# humidor_controller_v31.net
KiCad netlist of a schematic drawn in EAGLE
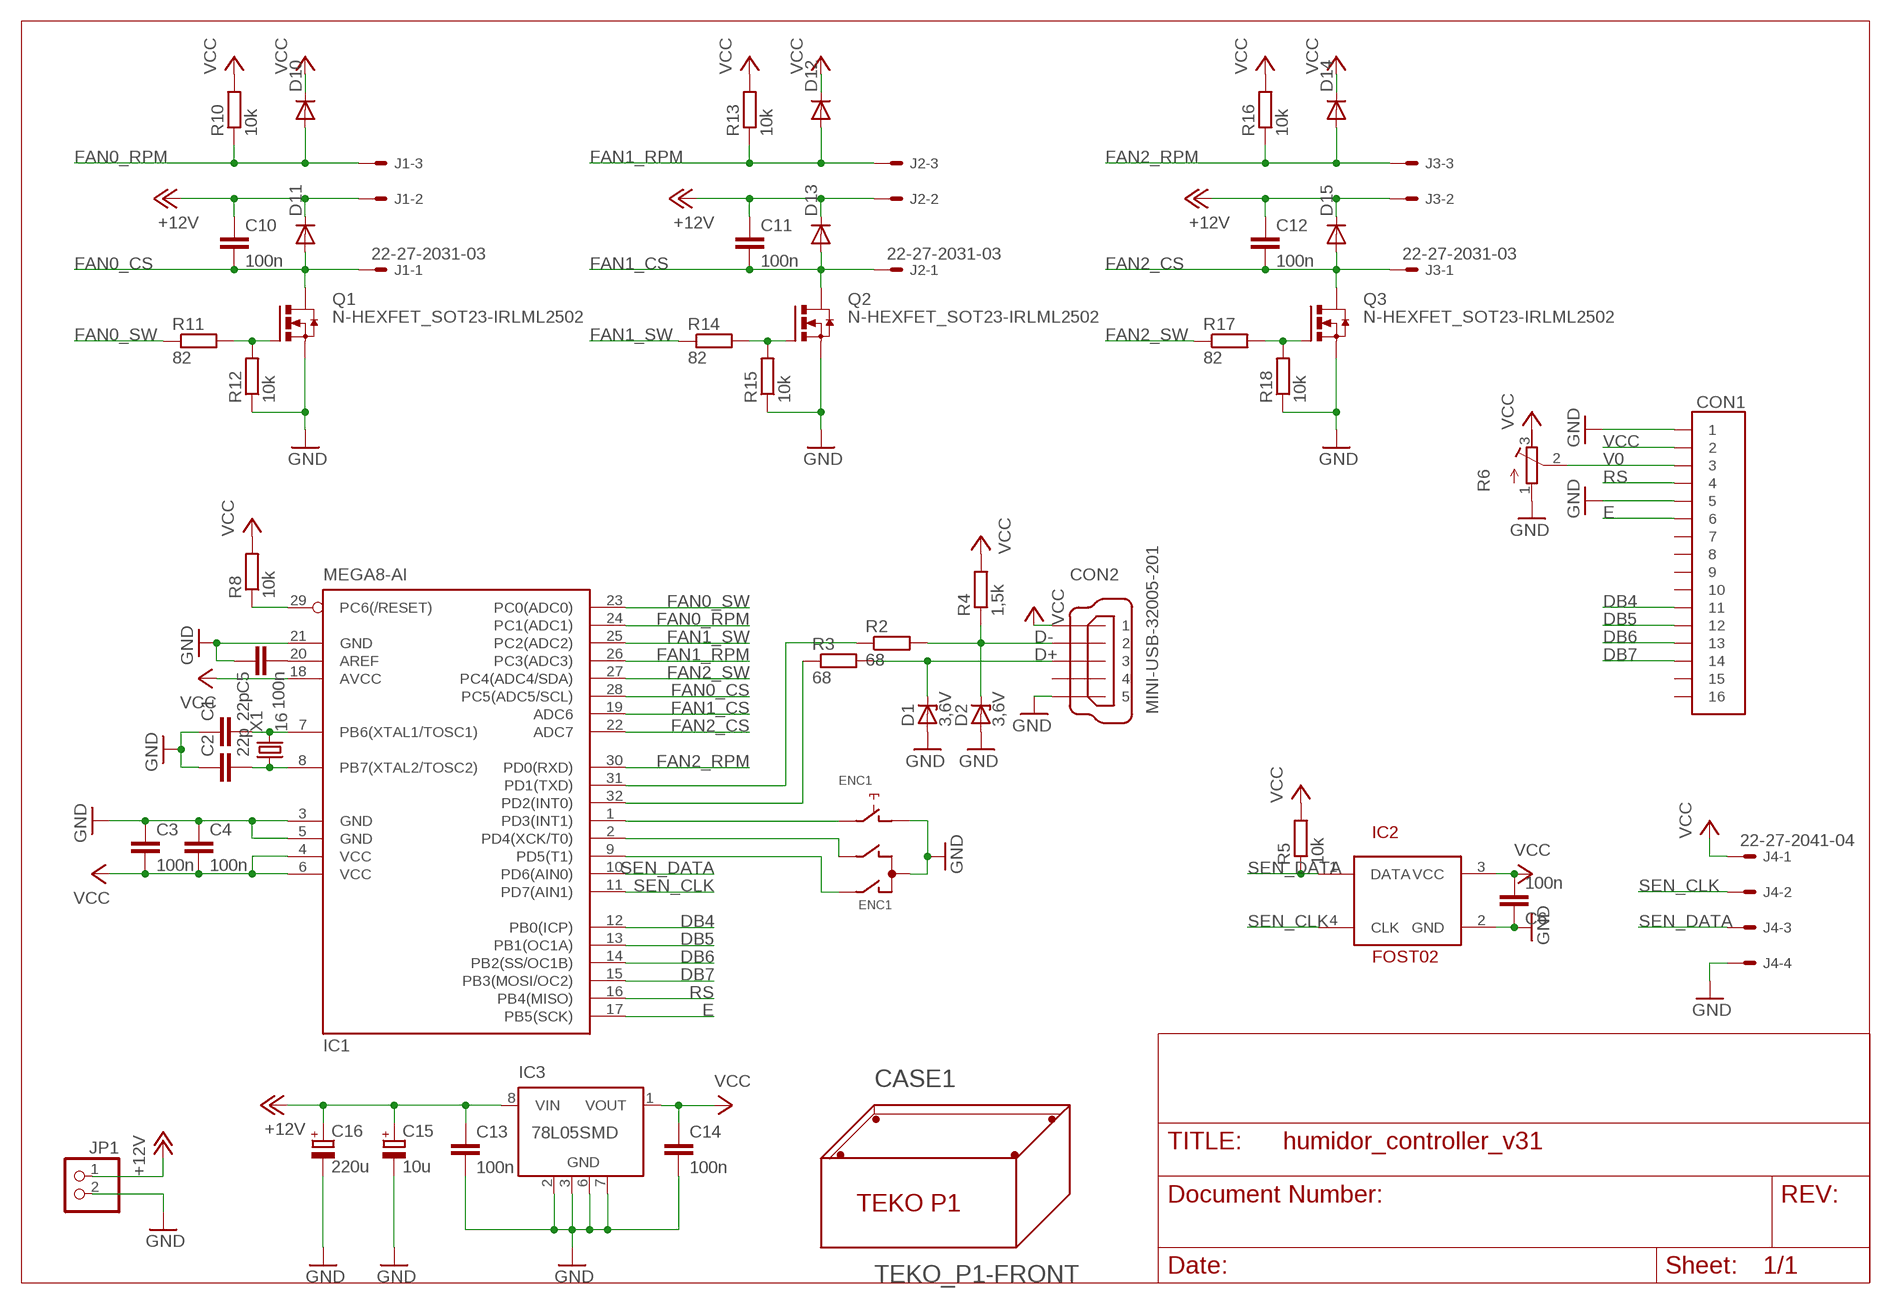
[diagram p0: schematic, sheet 1]

(export (version "E")
  (design (tool "Eeschema 10.0.6"))
  (components
    (comp (ref "C1")
      (value "22p")
      (footprint "eagle-import:C0805")
      (libsource (lib "eagle-import") (part "C-EUC0805"))
    )
    (comp (ref "C2")
      (value "22p")
      (footprint "eagle-import:C0805")
      (libsource (lib "eagle-import") (part "C-EUC0805"))
    )
    (comp (ref "C3")
      (value "100n")
      (footprint "eagle-import:C0805")
      (libsource (lib "eagle-import") (part "resistor_C-EUC0805"))
    )
    (comp (ref "C4")
      (value "100n")
      (footprint "eagle-import:C0805")
      (libsource (lib "eagle-import") (part "resistor_C-EUC0805"))
    )
    (comp (ref "C5")
      (value "100n")
      (footprint "eagle-import:C0805")
      (libsource (lib "eagle-import") (part "resistor_C-EUC0805"))
    )
    (comp (ref "C6")
      (value "100n")
      (footprint "eagle-import:C0805")
      (libsource (lib "eagle-import") (part "resistor_C-EUC0805"))
    )
    (comp (ref "C10")
      (value "100n")
      (footprint "eagle-import:C0805")
      (libsource (lib "eagle-import") (part "resistor_C-EUC0805"))
    )
    (comp (ref "C11")
      (value "100n")
      (footprint "eagle-import:C0805")
      (libsource (lib "eagle-import") (part "resistor_C-EUC0805"))
    )
    (comp (ref "C12")
      (value "100n")
      (footprint "eagle-import:C0805")
      (libsource (lib "eagle-import") (part "resistor_C-EUC0805"))
    )
    (comp (ref "C13")
      (value "100n")
      (footprint "eagle-import:C0805")
      (libsource (lib "eagle-import") (part "C-EUC0805"))
    )
    (comp (ref "C14")
      (value "100n")
      (footprint "eagle-import:C0805")
      (libsource (lib "eagle-import") (part "C-EUC0805"))
    )
    (comp (ref "C15")
      (value "10u")
      (footprint "eagle-import:PANASONIC_D")
      (libsource (lib "eagle-import") (part "CPOL-EUD"))
    )
    (comp (ref "C16")
      (value "220u")
      (footprint "eagle-import:PANASONIC_G")
      (libsource (lib "eagle-import") (part "CPOL-EUG"))
    )
    (comp (ref "CASE1")
      (value "TEKO_P1-FRONT")
      (footprint "eagle-import:TEKO_P1_FRONT")
      (libsource (lib "eagle-import") (part "TEKO_P1-FRONT"))
    )
    (comp (ref "CON1")
      (value "52207-16")
      (footprint "eagle-import:52207-16")
      (libsource (lib "eagle-import") (part "52207-16"))
    )
    (comp (ref "CON2")
      (value "MINI-USB-32005-201")
      (footprint "eagle-import:32005-201")
      (libsource (lib "eagle-import") (part "MINI-USB-32005-201"))
    )
    (comp (ref "D1")
      (value "3,6V")
      (footprint "eagle-import:SOD80C")
      (libsource (lib "eagle-import") (part "ZENER-DIODESOD80C"))
    )
    (comp (ref "D2")
      (value "3,6V")
      (footprint "eagle-import:SOD80C")
      (libsource (lib "eagle-import") (part "ZENER-DIODESOD80C"))
    )
    (comp (ref "D10")
      (value "DIODE-SOD323-R")
      (footprint "eagle-import:SOD323-R")
      (libsource (lib "eagle-import") (part "DIODE-SOD323-R"))
    )
    (comp (ref "D11")
      (value "DIODE-SOD323-R")
      (footprint "eagle-import:SOD323-R")
      (libsource (lib "eagle-import") (part "DIODE-SOD323-R"))
    )
    (comp (ref "D12")
      (value "DIODE-SOD323-R")
      (footprint "eagle-import:SOD323-R")
      (libsource (lib "eagle-import") (part "DIODE-SOD323-R"))
    )
    (comp (ref "D13")
      (value "DIODE-SOD323-R")
      (footprint "eagle-import:SOD323-R")
      (libsource (lib "eagle-import") (part "DIODE-SOD323-R"))
    )
    (comp (ref "D14")
      (value "DIODE-SOD323-R")
      (footprint "eagle-import:SOD323-R")
      (libsource (lib "eagle-import") (part "DIODE-SOD323-R"))
    )
    (comp (ref "D15")
      (value "DIODE-SOD323-R")
      (footprint "eagle-import:SOD323-R")
      (libsource (lib "eagle-import") (part "DIODE-SOD323-R"))
    )
    (comp (ref "ENC1")
      (value "NOBLE_RE0124")
      (footprint "eagle-import:RE0124")
      (libsource (lib "eagle-import") (part "NOBLE_RE0124"))
    )
    (comp (ref "IC1")
      (value "MEGA8-AI")
      (footprint "eagle-import:TQFP32-08")
      (libsource (lib "eagle-import") (part "MEGA8-AI"))
    )
    (comp (ref "IC2")
      (value "FOST02")
      (footprint "eagle-import:FOST02")
      (libsource (lib "eagle-import") (part "FOST02"))
    )
    (comp (ref "IC3")
      (value "78L05SMD")
      (footprint "eagle-import:SO08")
      (libsource (lib "eagle-import") (part "78LSMD05"))
    )
    (comp (ref "J1")
      (value "22-27-2031-03")
      (footprint "eagle-import:6410-03")
      (libsource (lib "eagle-import") (part "22-?-0327-2031"))
    )
    (comp (ref "J2")
      (value "22-27-2031-03")
      (footprint "eagle-import:6410-03")
      (libsource (lib "eagle-import") (part "22-?-0327-2031"))
    )
    (comp (ref "J3")
      (value "22-27-2031-03")
      (footprint "eagle-import:6410-03")
      (libsource (lib "eagle-import") (part "22-?-0327-2031"))
    )
    (comp (ref "J4")
      (value "22-27-2041-04")
      (footprint "eagle-import:6410-04")
      (libsource (lib "eagle-import") (part "22-?-0427-2041"))
    )
    (comp (ref "JP1")
      (value "PINHD-1X2")
      (footprint "eagle-import:1X02")
      (libsource (lib "eagle-import") (part "PINHD-1X2"))
    )
    (comp (ref "Q1")
      (value "N-HEXFET_SOT23-IRLML2502")
      (footprint "eagle-import:SOT23")
      (libsource (lib "eagle-import") (part "N-HEXFET_?-SOT23IRLML2502"))
    )
    (comp (ref "Q2")
      (value "N-HEXFET_SOT23-IRLML2502")
      (footprint "eagle-import:SOT23")
      (libsource (lib "eagle-import") (part "N-HEXFET_?-SOT23IRLML2502"))
    )
    (comp (ref "Q3")
      (value "N-HEXFET_SOT23-IRLML2502")
      (footprint "eagle-import:SOT23")
      (libsource (lib "eagle-import") (part "N-HEXFET_?-SOT23IRLML2502"))
    )
    (comp (ref "R2")
      (value "68")
      (footprint "eagle-import:R0805")
      (libsource (lib "eagle-import") (part "R-EU_R0805"))
    )
    (comp (ref "R3")
      (value "68")
      (footprint "eagle-import:R0805")
      (libsource (lib "eagle-import") (part "R-EU_R0805"))
    )
    (comp (ref "R4")
      (value "1,5k")
      (footprint "eagle-import:R0805")
      (libsource (lib "eagle-import") (part "R-EU_R0805"))
    )
    (comp (ref "R5")
      (value "10k")
      (footprint "eagle-import:R0805")
      (libsource (lib "eagle-import") (part "R-EU_R0805"))
    )
    (comp (ref "R6")
      (value "R-TRIMM4G/J")
      (footprint "eagle-import:RTRIM4G_J")
      (libsource (lib "eagle-import") (part "R-TRIMM4G/J"))
    )
    (comp (ref "R8")
      (value "10k")
      (footprint "eagle-import:R0805")
      (libsource (lib "eagle-import") (part "R-EU_R0805"))
    )
    (comp (ref "R10")
      (value "10k")
      (footprint "eagle-import:R0805")
      (libsource (lib "eagle-import") (part "R-EU_R0805"))
    )
    (comp (ref "R11")
      (value "82")
      (footprint "eagle-import:R0805")
      (libsource (lib "eagle-import") (part "R-EU_R0805"))
    )
    (comp (ref "R12")
      (value "10k")
      (footprint "eagle-import:R0805")
      (libsource (lib "eagle-import") (part "R-EU_R0805"))
    )
    (comp (ref "R13")
      (value "10k")
      (footprint "eagle-import:R0805")
      (libsource (lib "eagle-import") (part "R-EU_R0805"))
    )
    (comp (ref "R14")
      (value "82")
      (footprint "eagle-import:R0805")
      (libsource (lib "eagle-import") (part "R-EU_R0805"))
    )
    (comp (ref "R15")
      (value "10k")
      (footprint "eagle-import:R0805")
      (libsource (lib "eagle-import") (part "R-EU_R0805"))
    )
    (comp (ref "R16")
      (value "10k")
      (footprint "eagle-import:R0805")
      (libsource (lib "eagle-import") (part "R-EU_R0805"))
    )
    (comp (ref "R17")
      (value "82")
      (footprint "eagle-import:R0805")
      (libsource (lib "eagle-import") (part "R-EU_R0805"))
    )
    (comp (ref "R18")
      (value "10k")
      (footprint "eagle-import:R0805")
      (libsource (lib "eagle-import") (part "R-EU_R0805"))
    )
    (comp (ref "X1")
      (value "16")
      (footprint "eagle-import:HC49UP")
      (libsource (lib "eagle-import") (part "CRYSTALHC49UP"))
    )
  )
  (nets
    (net (code "1") (name "+12V") (class "Default")
      (node (ref "C10") (pin "1") (pinfunction "1_1") (pintype "passive"))
      (node (ref "C11") (pin "1") (pinfunction "1_1") (pintype "passive"))
      (node (ref "C12") (pin "1") (pinfunction "1_1") (pintype "passive"))
      (node (ref "C13") (pin "1") (pinfunction "1_1") (pintype "passive"))
      (node (ref "C15") (pin "+") (pinfunction "+_+") (pintype "passive"))
      (node (ref "C16") (pin "+") (pinfunction "+_+") (pintype "passive"))
      (node (ref "D11") (pin "C") (pinfunction "C_C") (pintype "passive"))
      (node (ref "D13") (pin "C") (pinfunction "C_C") (pintype "passive"))
      (node (ref "D15") (pin "C") (pinfunction "C_C") (pintype "passive"))
      (node (ref "IC3") (pin "8") (pinfunction "VIN_8") (pintype "passive"))
      (node (ref "J1") (pin "2") (pinfunction "S_2") (pintype "passive"))
      (node (ref "J2") (pin "2") (pinfunction "S_2") (pintype "passive"))
      (node (ref "J3") (pin "2") (pinfunction "S_2") (pintype "passive"))
      (node (ref "JP1") (pin "1") (pinfunction "1_1") (pintype "passive"))
    )
    (net (code "2") (name "/D+") (class "Default")
      (node (ref "CON2") (pin "3") (pinfunction "3_3") (pintype "passive"))
      (node (ref "D1") (pin "C") (pinfunction "C_C") (pintype "passive"))
      (node (ref "R3") (pin "2") (pinfunction "2_2") (pintype "passive"))
    )
    (net (code "3") (name "/D-") (class "Default")
      (node (ref "CON2") (pin "2") (pinfunction "2_2") (pintype "passive"))
      (node (ref "D2") (pin "C") (pinfunction "C_C") (pintype "passive"))
      (node (ref "R2") (pin "2") (pinfunction "2_2") (pintype "passive"))
      (node (ref "R4") (pin "1") (pinfunction "1_1") (pintype "passive"))
    )
    (net (code "4") (name "/DB4") (class "Default")
      (node (ref "CON1") (pin "11") (pinfunction "11_11") (pintype "bidirectional"))
      (node (ref "IC1") (pin "12") (pinfunction "PB0(ICP)_12") (pintype "bidirectional"))
    )
    (net (code "5") (name "/DB5") (class "Default")
      (node (ref "CON1") (pin "12") (pinfunction "12_12") (pintype "bidirectional"))
      (node (ref "IC1") (pin "13") (pinfunction "PB1(OC1A)_13") (pintype "bidirectional"))
    )
    (net (code "6") (name "/DB6") (class "Default")
      (node (ref "CON1") (pin "13") (pinfunction "13_13") (pintype "bidirectional"))
      (node (ref "IC1") (pin "14") (pinfunction "PB2(SS/OC1B)_14") (pintype "bidirectional"))
    )
    (net (code "7") (name "/DB7") (class "Default")
      (node (ref "CON1") (pin "14") (pinfunction "14_14") (pintype "bidirectional"))
      (node (ref "IC1") (pin "15") (pinfunction "PB3(MOSI/OC2)_15") (pintype "bidirectional"))
    )
    (net (code "8") (name "/E") (class "Default")
      (node (ref "CON1") (pin "6") (pinfunction "6_6") (pintype "bidirectional"))
      (node (ref "IC1") (pin "17") (pinfunction "PB5(SCK)_17") (pintype "bidirectional"))
    )
    (net (code "9") (name "/FAN0_CS") (class "Default")
      (node (ref "C10") (pin "2") (pinfunction "2_2") (pintype "passive"))
      (node (ref "D11") (pin "A") (pinfunction "A_A") (pintype "passive"))
      (node (ref "IC1") (pin "28") (pinfunction "PC5(ADC5/SCL)_28") (pintype "bidirectional"))
      (node (ref "J1") (pin "1") (pinfunction "S_1") (pintype "passive"))
      (node (ref "Q1") (pin "3") (pinfunction "D_3") (pintype "passive"))
    )
    (net (code "10") (name "/FAN0_RPM") (class "Default")
      (node (ref "D10") (pin "A") (pinfunction "A_A") (pintype "passive"))
      (node (ref "IC1") (pin "24") (pinfunction "PC1(ADC1)_24") (pintype "bidirectional"))
      (node (ref "J1") (pin "3") (pinfunction "S_3") (pintype "passive"))
      (node (ref "R10") (pin "1") (pinfunction "1_1") (pintype "passive"))
    )
    (net (code "11") (name "/FAN0_SW") (class "Default")
      (node (ref "IC1") (pin "23") (pinfunction "PC0(ADC0)_23") (pintype "bidirectional"))
      (node (ref "R11") (pin "1") (pinfunction "1_1") (pintype "passive"))
    )
    (net (code "12") (name "/FAN1_CS") (class "Default")
      (node (ref "C11") (pin "2") (pinfunction "2_2") (pintype "passive"))
      (node (ref "D13") (pin "A") (pinfunction "A_A") (pintype "passive"))
      (node (ref "IC1") (pin "19") (pinfunction "ADC6_19") (pintype "bidirectional"))
      (node (ref "J2") (pin "1") (pinfunction "S_1") (pintype "passive"))
      (node (ref "Q2") (pin "3") (pinfunction "D_3") (pintype "passive"))
    )
    (net (code "13") (name "/FAN1_RPM") (class "Default")
      (node (ref "D12") (pin "A") (pinfunction "A_A") (pintype "passive"))
      (node (ref "IC1") (pin "26") (pinfunction "PC3(ADC3)_26") (pintype "bidirectional"))
      (node (ref "J2") (pin "3") (pinfunction "S_3") (pintype "passive"))
      (node (ref "R13") (pin "1") (pinfunction "1_1") (pintype "passive"))
    )
    (net (code "14") (name "/FAN1_SW") (class "Default")
      (node (ref "IC1") (pin "25") (pinfunction "PC2(ADC2)_25") (pintype "bidirectional"))
      (node (ref "R14") (pin "1") (pinfunction "1_1") (pintype "passive"))
    )
    (net (code "15") (name "/FAN2_CS") (class "Default")
      (node (ref "C12") (pin "2") (pinfunction "2_2") (pintype "passive"))
      (node (ref "D15") (pin "A") (pinfunction "A_A") (pintype "passive"))
      (node (ref "IC1") (pin "22") (pinfunction "ADC7_22") (pintype "bidirectional"))
      (node (ref "J3") (pin "1") (pinfunction "S_1") (pintype "passive"))
      (node (ref "Q3") (pin "3") (pinfunction "D_3") (pintype "passive"))
    )
    (net (code "16") (name "/FAN2_RPM") (class "Default")
      (node (ref "D14") (pin "A") (pinfunction "A_A") (pintype "passive"))
      (node (ref "IC1") (pin "30") (pinfunction "PD0(RXD)_30") (pintype "bidirectional"))
      (node (ref "J3") (pin "3") (pinfunction "S_3") (pintype "passive"))
      (node (ref "R16") (pin "1") (pinfunction "1_1") (pintype "passive"))
    )
    (net (code "17") (name "/FAN2_SW") (class "Default")
      (node (ref "IC1") (pin "27") (pinfunction "PC4(ADC4/SDA)_27") (pintype "bidirectional"))
      (node (ref "R17") (pin "1") (pinfunction "1_1") (pintype "passive"))
    )
    (net (code "18") (name "/RS") (class "Default")
      (node (ref "CON1") (pin "4") (pinfunction "4_4") (pintype "bidirectional"))
      (node (ref "IC1") (pin "16") (pinfunction "PB4(MISO)_16") (pintype "bidirectional"))
    )
    (net (code "19") (name "/SEN_CLK") (class "Default")
      (node (ref "IC1") (pin "11") (pinfunction "PD7(AIN1)_11") (pintype "bidirectional"))
      (node (ref "IC2") (pin "4") (pinfunction "CLK_4") (pintype "input"))
      (node (ref "J4") (pin "2") (pinfunction "S_2") (pintype "passive"))
    )
    (net (code "20") (name "/SEN_DATA") (class "Default")
      (node (ref "IC1") (pin "10") (pinfunction "PD6(AIN0)_10") (pintype "bidirectional"))
      (node (ref "IC2") (pin "1") (pinfunction "DATA_1") (pintype "bidirectional"))
      (node (ref "J4") (pin "3") (pinfunction "S_3") (pintype "passive"))
      (node (ref "R5") (pin "1") (pinfunction "1_1") (pintype "passive"))
    )
    (net (code "21") (name "/V0") (class "Default")
      (node (ref "CON1") (pin "3") (pinfunction "3_3") (pintype "bidirectional"))
      (node (ref "R6") (pin "2") (pinfunction "S_2") (pintype "passive"))
    )
    (net (code "22") (name "GND") (class "Default")
      (node (ref "C1") (pin "1") (pinfunction "1_1") (pintype "passive"))
      (node (ref "C13") (pin "2") (pinfunction "2_2") (pintype "passive"))
      (node (ref "C14") (pin "2") (pinfunction "2_2") (pintype "passive"))
      (node (ref "C15") (pin "-") (pinfunction "-_-") (pintype "passive"))
      (node (ref "C16") (pin "-") (pinfunction "-_-") (pintype "passive"))
      (node (ref "C2") (pin "1") (pinfunction "1_1") (pintype "passive"))
      (node (ref "C3") (pin "1") (pinfunction "1_1") (pintype "passive"))
      (node (ref "C4") (pin "1") (pinfunction "1_1") (pintype "passive"))
      (node (ref "C5") (pin "1") (pinfunction "1_1") (pintype "passive"))
      (node (ref "C6") (pin "1") (pinfunction "1_1") (pintype "passive"))
      (node (ref "CON1") (pin "1") (pinfunction "1_1") (pintype "bidirectional"))
      (node (ref "CON1") (pin "5") (pinfunction "5_5") (pintype "bidirectional"))
      (node (ref "CON2") (pin "5") (pinfunction "5_5") (pintype "passive"))
      (node (ref "D1") (pin "A") (pinfunction "A_A") (pintype "passive"))
      (node (ref "D2") (pin "A") (pinfunction "A_A") (pintype "passive"))
      (node (ref "ENC1") (pin "+") (pinfunction "1_+") (pintype "passive"))
      (node (ref "ENC1") (pin "C") (pinfunction "C_C") (pintype "passive"))
      (node (ref "IC1") (pin "21") (pinfunction "GND_21") (pintype "power_in"))
      (node (ref "IC1") (pin "3") (pinfunction "GND_3") (pintype "power_in"))
      (node (ref "IC1") (pin "5") (pinfunction "GND_5") (pintype "power_in"))
      (node (ref "IC2") (pin "2") (pinfunction "GND_2") (pintype "power_in"))
      (node (ref "IC3") (pin "2") (pinfunction "GND_2") (pintype "power_in"))
      (node (ref "IC3") (pin "3") (pinfunction "GND_3") (pintype "power_in"))
      (node (ref "IC3") (pin "6") (pinfunction "GND_6") (pintype "power_in"))
      (node (ref "IC3") (pin "7") (pinfunction "GND_7") (pintype "power_in"))
      (node (ref "J4") (pin "4") (pinfunction "S_4") (pintype "passive"))
      (node (ref "JP1") (pin "2") (pinfunction "2_2") (pintype "passive"))
      (node (ref "Q1") (pin "2") (pinfunction "S_2") (pintype "passive"))
      (node (ref "Q2") (pin "2") (pinfunction "S_2") (pintype "passive"))
      (node (ref "Q3") (pin "2") (pinfunction "S_2") (pintype "passive"))
      (node (ref "R12") (pin "1") (pinfunction "1_1") (pintype "passive"))
      (node (ref "R15") (pin "1") (pinfunction "1_1") (pintype "passive"))
      (node (ref "R18") (pin "1") (pinfunction "1_1") (pintype "passive"))
      (node (ref "R6") (pin "1") (pinfunction "E_1") (pintype "passive"))
    )
    (net (code "23") (name "Net-(ENC1B-2)") (class "Default")
      (node (ref "ENC1") (pin "-") (pinfunction "2_-") (pintype "passive"))
      (node (ref "IC1") (pin "1") (pinfunction "PD3(INT1)_1") (pintype "bidirectional"))
    )
    (net (code "24") (name "Net-(IC1-AREF)") (class "Default")
      (node (ref "C5") (pin "2") (pinfunction "2_2") (pintype "passive"))
      (node (ref "IC1") (pin "20") (pinfunction "AREF_20") (pintype "passive"))
    )
    (net (code "25") (name "Net-(IC1-PB6(XTAL1{slash}TOSC1))") (class "Default")
      (node (ref "C1") (pin "2") (pinfunction "2_2") (pintype "passive"))
      (node (ref "IC1") (pin "7") (pinfunction "PB6(XTAL1/TOSC1)_7") (pintype "bidirectional"))
      (node (ref "X1") (pin "2") (pinfunction "2_2") (pintype "passive"))
    )
    (net (code "26") (name "Net-(IC1-PB7(XTAL2{slash}TOSC2))") (class "Default")
      (node (ref "C2") (pin "2") (pinfunction "2_2") (pintype "passive"))
      (node (ref "IC1") (pin "8") (pinfunction "PB7(XTAL2/TOSC2)_8") (pintype "bidirectional"))
      (node (ref "X1") (pin "1") (pinfunction "1_1") (pintype "passive"))
    )
    (net (code "27") (name "Net-(IC1-PC6({slash}RESET))") (class "Default")
      (node (ref "IC1") (pin "29") (pinfunction "PC6(/RESET)_29") (pintype "bidirectional"))
      (node (ref "R8") (pin "1") (pinfunction "1_1") (pintype "passive"))
    )
    (net (code "28") (name "Net-(IC1-PD1(TXD))") (class "Default")
      (node (ref "IC1") (pin "31") (pinfunction "PD1(TXD)_31") (pintype "bidirectional"))
      (node (ref "R2") (pin "1") (pinfunction "1_1") (pintype "passive"))
    )
    (net (code "29") (name "Net-(IC1-PD2(INT0))") (class "Default")
      (node (ref "IC1") (pin "32") (pinfunction "PD2(INT0)_32") (pintype "bidirectional"))
      (node (ref "R3") (pin "1") (pinfunction "1_1") (pintype "passive"))
    )
    (net (code "30") (name "Net-(IC1-PD4(XCK{slash}T0))") (class "Default")
      (node (ref "ENC1") (pin "B") (pinfunction "B_B") (pintype "passive"))
      (node (ref "IC1") (pin "2") (pinfunction "PD4(XCK/T0)_2") (pintype "bidirectional"))
    )
    (net (code "31") (name "Net-(IC1-PD5(T1))") (class "Default")
      (node (ref "ENC1") (pin "A") (pinfunction "A_A") (pintype "passive"))
      (node (ref "IC1") (pin "9") (pinfunction "PD5(T1)_9") (pintype "bidirectional"))
    )
    (net (code "32") (name "Net-(Q1-G)") (class "Default")
      (node (ref "Q1") (pin "1") (pinfunction "G_1") (pintype "passive"))
      (node (ref "R11") (pin "2") (pinfunction "2_2") (pintype "passive"))
      (node (ref "R12") (pin "2") (pinfunction "2_2") (pintype "passive"))
    )
    (net (code "33") (name "Net-(Q2-G)") (class "Default")
      (node (ref "Q2") (pin "1") (pinfunction "G_1") (pintype "passive"))
      (node (ref "R14") (pin "2") (pinfunction "2_2") (pintype "passive"))
      (node (ref "R15") (pin "2") (pinfunction "2_2") (pintype "passive"))
    )
    (net (code "34") (name "Net-(Q3-G)") (class "Default")
      (node (ref "Q3") (pin "1") (pinfunction "G_1") (pintype "passive"))
      (node (ref "R17") (pin "2") (pinfunction "2_2") (pintype "passive"))
      (node (ref "R18") (pin "2") (pinfunction "2_2") (pintype "passive"))
    )
    (net (code "35") (name "VCC") (class "Default")
      (node (ref "C14") (pin "1") (pinfunction "1_1") (pintype "passive"))
      (node (ref "C3") (pin "2") (pinfunction "2_2") (pintype "passive"))
      (node (ref "C4") (pin "2") (pinfunction "2_2") (pintype "passive"))
      (node (ref "C6") (pin "2") (pinfunction "2_2") (pintype "passive"))
      (node (ref "CON1") (pin "2") (pinfunction "2_2") (pintype "bidirectional"))
      (node (ref "CON2") (pin "1") (pinfunction "1_1") (pintype "passive"))
      (node (ref "D10") (pin "C") (pinfunction "C_C") (pintype "passive"))
      (node (ref "D12") (pin "C") (pinfunction "C_C") (pintype "passive"))
      (node (ref "D14") (pin "C") (pinfunction "C_C") (pintype "passive"))
      (node (ref "IC1") (pin "18") (pinfunction "AVCC_18") (pintype "power_in"))
      (node (ref "IC1") (pin "4") (pinfunction "VCC_4") (pintype "power_in"))
      (node (ref "IC1") (pin "6") (pinfunction "VCC_6") (pintype "power_in"))
      (node (ref "IC2") (pin "3") (pinfunction "VCC_3") (pintype "power_in"))
      (node (ref "IC3") (pin "1") (pinfunction "VOUT_1") (pintype "output"))
      (node (ref "J4") (pin "1") (pinfunction "S_1") (pintype "passive"))
      (node (ref "R10") (pin "2") (pinfunction "2_2") (pintype "passive"))
      (node (ref "R13") (pin "2") (pinfunction "2_2") (pintype "passive"))
      (node (ref "R16") (pin "2") (pinfunction "2_2") (pintype "passive"))
      (node (ref "R4") (pin "2") (pinfunction "2_2") (pintype "passive"))
      (node (ref "R5") (pin "2") (pinfunction "2_2") (pintype "passive"))
      (node (ref "R6") (pin "3") (pinfunction "A_3") (pintype "passive"))
      (node (ref "R8") (pin "2") (pinfunction "2_2") (pintype "passive"))
    )
    (net (code "36") (name "unconnected-(CON1-Pad7)") (class "Default")
      (node (ref "CON1") (pin "7") (pinfunction "7_7") (pintype "bidirectional"))
    )
    (net (code "37") (name "unconnected-(CON1-Pad8)") (class "Default")
      (node (ref "CON1") (pin "8") (pinfunction "8_8") (pintype "bidirectional"))
    )
    (net (code "38") (name "unconnected-(CON1-Pad9)") (class "Default")
      (node (ref "CON1") (pin "9") (pinfunction "9_9") (pintype "bidirectional"))
    )
    (net (code "39") (name "unconnected-(CON1-Pad10)") (class "Default")
      (node (ref "CON1") (pin "10") (pinfunction "10_10") (pintype "bidirectional"))
    )
    (net (code "40") (name "unconnected-(CON1-Pad15)") (class "Default")
      (node (ref "CON1") (pin "15") (pinfunction "15_15") (pintype "bidirectional"))
    )
    (net (code "41") (name "unconnected-(CON1-Pad16)") (class "Default")
      (node (ref "CON1") (pin "16") (pinfunction "16_16") (pintype "bidirectional"))
    )
    (net (code "42") (name "unconnected-(CON2-Pad4)") (class "Default")
      (node (ref "CON2") (pin "4") (pinfunction "4_4") (pintype "passive"))
    )
  )
)
